# 04_Schematic.net
KiCad netlist of a schematic drawn in Altium Designer
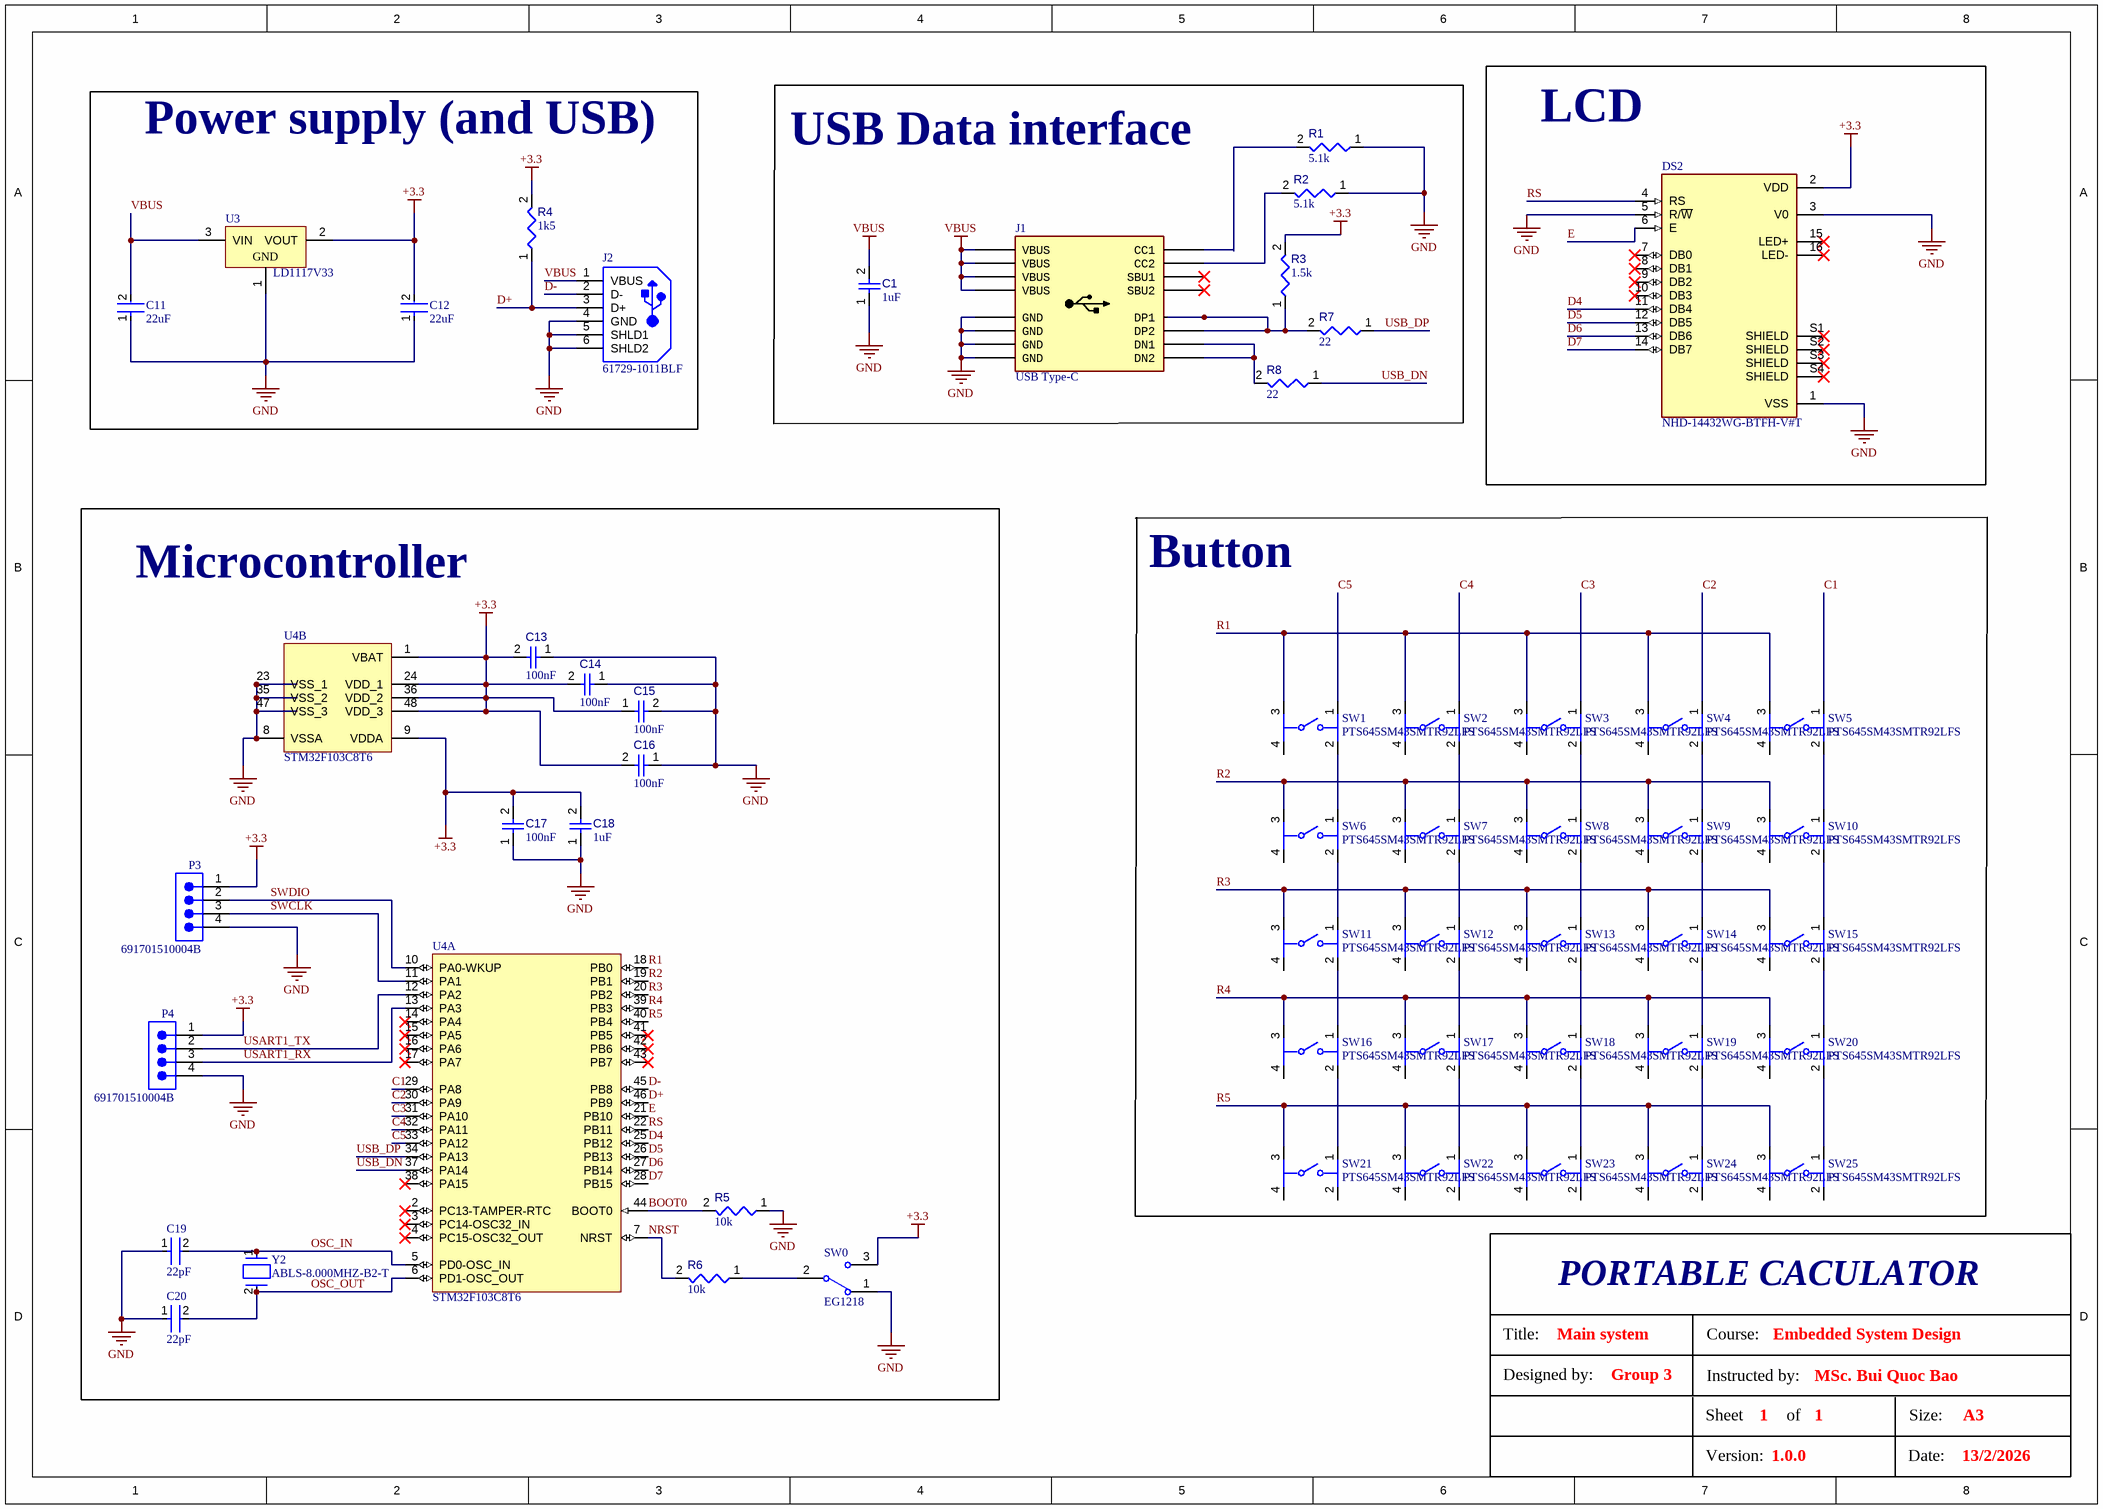
[diagram p0: 04_Schematic.SchDoc]

(export (version "E")
  (design (tool "Eeschema 10.0.6"))
  (components
    (comp (ref "C1")
      (value "1uF")
      (footprint "CAPC1005X56X25LL10T15")
      (description "Chip Capacitor, 0.1 uF, +/- 5%, 16 V, 0402 (1005 Metric)")
      (fields (field (name "TOLERANCE") "5%") (field (name "Comment") "Capacitor 0.1 uF +/- 5% 16 V 0402"))
      (libsource (lib "Nguyen Thaizeroxz") (part "CAP-NP-2"))
    )
    (comp (ref "C11")
      (value "22uF")
      (footprint "FP-RCE0K1-MFG")
      (description "Cap Ceramic 22pF 50V C0G ±5% Radial 5mm +125°C Automotive Bulk")
      (fields (field (name "TOLERANCE") "5%"))
      (libsource (lib "Altium Content Vault") (part "b4654b650e69147ec39a6b967a45e02"))
    )
    (comp (ref "C12")
      (value "22uF")
      (footprint "FP-RCE0K1-MFG")
      (description "Cap Ceramic 22pF 50V C0G ±5% Radial 5mm +125°C Automotive Bulk")
      (fields (field (name "TOLERANCE") "5%"))
      (libsource (lib "Altium Content Vault") (part "b4654b650e69147ec39a6b967a45e02"))
    )
    (comp (ref "C13")
      (value "100nF")
      (footprint "CAPC1005X56X25LL10T15")
      (description "Chip Capacitor, 0.1 uF, +/- 5%, 16 V, 0402 (1005 Metric)")
      (fields (field (name "TOLERANCE") "5%") (field (name "Comment") "Capacitor 0.1 uF +/- 5% 16 V 0402"))
      (libsource (lib "Nguyen Thaizeroxz") (part "CAP-NP-2"))
    )
    (comp (ref "C14")
      (value "100nF")
      (footprint "CAPC1005X56X25LL10T15")
      (description "Chip Capacitor, 0.1 uF, +/- 5%, 16 V, 0402 (1005 Metric)")
      (fields (field (name "TOLERANCE") "5%") (field (name "Comment") "Capacitor 0.1 uF +/- 5% 16 V 0402"))
      (libsource (lib "Nguyen Thaizeroxz") (part "CAP-NP-2"))
    )
    (comp (ref "C15")
      (value "100nF")
      (footprint "CAPC1005X56X25LL10T15")
      (description "Chip Capacitor, 0.1 uF, +/- 5%, 16 V, 0402 (1005 Metric)")
      (fields (field (name "TOLERANCE") "5%") (field (name "Comment") "Capacitor 0.1 uF +/- 5% 16 V 0402"))
      (libsource (lib "Nguyen Thaizeroxz") (part "CAP-NP-2"))
    )
    (comp (ref "C16")
      (value "100nF")
      (footprint "CAPC1005X56X25LL10T15")
      (description "Chip Capacitor, 0.1 uF, +/- 5%, 16 V, 0402 (1005 Metric)")
      (fields (field (name "TOLERANCE") "5%") (field (name "Comment") "Capacitor 0.1 uF +/- 5% 16 V 0402"))
      (libsource (lib "Nguyen Thaizeroxz") (part "CAP-NP-2"))
    )
    (comp (ref "C17")
      (value "100nF")
      (footprint "CAPC1005X56X25LL10T15")
      (description "Chip Capacitor, 0.1 uF, +/- 5%, 16 V, 0402 (1005 Metric)")
      (fields (field (name "TOLERANCE") "5%") (field (name "Comment") "Capacitor 0.1 uF +/- 5% 16 V 0402"))
      (libsource (lib "Nguyen Thaizeroxz") (part "CAP-NP-2"))
    )
    (comp (ref "C18")
      (value "1uF")
      (footprint "CAPC1005X56X25LL10T15")
      (description "Chip Capacitor, 0.1 uF, +/- 5%, 16 V, 0402 (1005 Metric)")
      (fields (field (name "TOLERANCE") "5%") (field (name "Comment") "Capacitor 0.1 uF +/- 5% 16 V 0402"))
      (libsource (lib "Nguyen Thaizeroxz") (part "CAP-NP-2"))
    )
    (comp (ref "C19")
      (value "22pF")
      (footprint "FP-RCE0K1-MFG")
      (description "Cap Ceramic 22pF 50V C0G ±5% Radial 5mm +125°C Automotive Bulk")
      (fields (field (name "TOLERANCE") "5%"))
      (libsource (lib "Altium Content Vault") (part "b4654b650e69147ec39a6b967a45e02"))
    )
    (comp (ref "C20")
      (value "22pF")
      (footprint "FP-RCE0K1-MFG")
      (description "Cap Ceramic 22pF 50V C0G ±5% Radial 5mm +125°C Automotive Bulk")
      (fields (field (name "TOLERANCE") "5%"))
      (libsource (lib "Altium Content Vault") (part "b4654b650e69147ec39a6b967a45e02"))
    )
    (comp (ref "DS2")
      (value "NHD-14432WG-BTFH-V#T")
      (footprint "LCD_NHD-14432WG-BTFH-V#T")
      (fields (field (name "MF") "Newhaven Display"))
      (libsource (lib "Nguyen Thaizeroxz") (part "NHD-14432WG-BTFH-V#T"))
    )
    (comp (ref "J1")
      (value "USB Type-C")
      (footprint "TYPE-C-16POS")
      (libsource (lib "Schlib1") (part "USB Type-C"))
    )
    (comp (ref "J2")
      (value "61729-1011BLF")
      (footprint "FCI-61729-1011BLF_V")
      (description "USB Receptacle B Type, Right Angle, 4 Position, Height 11.5 mm,-40 to 85 degC, RoHS, Tube")
      (fields (field (name "MANUFACTURER") "FCI Electronics"))
      (libsource (lib "Nguyen Thaizeroxz") (part "USB-4-2SHLD"))
    )
    (comp (ref "P3")
      (value "691701510004B")
      (footprint "691701510004B")
      (description "Terminal Block, 5.08MM, Close Vertical Pcb Header, Thr Type, 4 Pins")
      (libsource (lib "Altium Content Vault") (part "TBL - 1R - 04P - Male"))
    )
    (comp (ref "P4")
      (value "691701510004B")
      (footprint "691701510004B")
      (description "Terminal Block, 5.08MM, Close Vertical Pcb Header, Thr Type, 4 Pins")
      (libsource (lib "Altium Content Vault") (part "TBL - 1R - 04P - Male"))
    )
    (comp (ref "R1")
      (value "5.1k")
      (footprint "RESC0402(1005)_L")
      (description "Chip Resistor, 1 kOhms, +/-5 %, 63 mW, -55 to 155 degC, 0402")
      (fields (field (name "TOLERANCE") "5%") (field (name "POWER") "63mW"))
      (libsource (lib "Nguyen Thaizeroxz") (part "RES-2"))
    )
    (comp (ref "R2")
      (value "5.1k")
      (footprint "RESC0402(1005)_L")
      (description "Chip Resistor, 1 kOhms, +/-5 %, 63 mW, -55 to 155 degC, 0402")
      (fields (field (name "TOLERANCE") "5%") (field (name "POWER") "63mW"))
      (libsource (lib "Nguyen Thaizeroxz") (part "RES-2"))
    )
    (comp (ref "R3")
      (value "1.5k")
      (footprint "RESC0402(1005)_L")
      (description "Chip Resistor, 1 kOhms, +/-5 %, 63 mW, -55 to 155 degC, 0402")
      (fields (field (name "TOLERANCE") "5%") (field (name "POWER") "63mW"))
      (libsource (lib "Nguyen Thaizeroxz") (part "RES-2"))
    )
    (comp (ref "R4")
      (value "1k5")
      (footprint "RESC0402(1005)_L")
      (description "Chip Resistor, 1 kOhms, +/-5 %, 63 mW, -55 to 155 degC, 0402")
      (fields (field (name "TOLERANCE") "5%") (field (name "POWER") "63mW"))
      (libsource (lib "Nguyen Thaizeroxz") (part "RES-2"))
    )
    (comp (ref "R5")
      (value "10k")
      (footprint "RESC0402(1005)_L")
      (description "Chip Resistor, 1 kOhms, +/-5 %, 63 mW, -55 to 155 degC, 0402")
      (fields (field (name "TOLERANCE") "5%") (field (name "POWER") "63mW"))
      (libsource (lib "Nguyen Thaizeroxz") (part "RES-2"))
    )
    (comp (ref "R6")
      (value "10k")
      (footprint "RESC0402(1005)_L")
      (description "Chip Resistor, 1 kOhms, +/-5 %, 63 mW, -55 to 155 degC, 0402")
      (fields (field (name "TOLERANCE") "5%") (field (name "POWER") "63mW"))
      (libsource (lib "Nguyen Thaizeroxz") (part "RES-2"))
    )
    (comp (ref "R7")
      (value "22")
      (footprint "RESC0402(1005)_L")
      (description "Chip Resistor, 1 kOhms, +/-5 %, 63 mW, -55 to 155 degC, 0402")
      (fields (field (name "TOLERANCE") "5%") (field (name "POWER") "63mW"))
      (libsource (lib "Nguyen Thaizeroxz") (part "RES-2"))
    )
    (comp (ref "R8")
      (value "22")
      (footprint "RESC0402(1005)_L")
      (description "Chip Resistor, 1 kOhms, +/-5 %, 63 mW, -55 to 155 degC, 0402")
      (fields (field (name "TOLERANCE") "5%") (field (name "POWER") "63mW"))
      (libsource (lib "Nguyen Thaizeroxz") (part "RES-2"))
    )
    (comp (ref "SW0")
      (value "EG1218")
      (footprint "ESWI-EG1218_V")
      (description "Slide Switch, SPDT, 500 V, -20 to 70 degC, 3-Pin THD, RoHS, Bulk")
      (fields (field (name "MANUFACTURER") "E-Switch"))
      (libsource (lib "Nguyen Thaizeroxz") (part "SW-SPDT-3_B"))
    )
    (comp (ref "SW1")
      (value "PTS645SM43SMTR92LFS")
      (footprint "FP-PTS645SM43SMTR92LFS-MFG")
      (description "SWITCH TACTILE SPST-NO 0.05A 12V")
      (libsource (lib "Altium Content Vault") (part "1adf0dd01260c80cf25a44bfd6b99ba"))
    )
    (comp (ref "SW2")
      (value "PTS645SM43SMTR92LFS")
      (footprint "FP-PTS645SM43SMTR92LFS-MFG")
      (description "SWITCH TACTILE SPST-NO 0.05A 12V")
      (libsource (lib "Altium Content Vault") (part "1adf0dd01260c80cf25a44bfd6b99ba"))
    )
    (comp (ref "SW3")
      (value "PTS645SM43SMTR92LFS")
      (footprint "FP-PTS645SM43SMTR92LFS-MFG")
      (description "SWITCH TACTILE SPST-NO 0.05A 12V")
      (libsource (lib "Altium Content Vault") (part "1adf0dd01260c80cf25a44bfd6b99ba"))
    )
    (comp (ref "SW4")
      (value "PTS645SM43SMTR92LFS")
      (footprint "FP-PTS645SM43SMTR92LFS-MFG")
      (description "SWITCH TACTILE SPST-NO 0.05A 12V")
      (libsource (lib "Altium Content Vault") (part "1adf0dd01260c80cf25a44bfd6b99ba"))
    )
    (comp (ref "SW5")
      (value "PTS645SM43SMTR92LFS")
      (footprint "FP-PTS645SM43SMTR92LFS-MFG")
      (description "SWITCH TACTILE SPST-NO 0.05A 12V")
      (libsource (lib "Altium Content Vault") (part "1adf0dd01260c80cf25a44bfd6b99ba"))
    )
    (comp (ref "SW6")
      (value "PTS645SM43SMTR92LFS")
      (footprint "FP-PTS645SM43SMTR92LFS-MFG")
      (description "SWITCH TACTILE SPST-NO 0.05A 12V")
      (libsource (lib "Altium Content Vault") (part "1adf0dd01260c80cf25a44bfd6b99ba"))
    )
    (comp (ref "SW7")
      (value "PTS645SM43SMTR92LFS")
      (footprint "FP-PTS645SM43SMTR92LFS-MFG")
      (description "SWITCH TACTILE SPST-NO 0.05A 12V")
      (libsource (lib "Altium Content Vault") (part "1adf0dd01260c80cf25a44bfd6b99ba"))
    )
    (comp (ref "SW8")
      (value "PTS645SM43SMTR92LFS")
      (footprint "FP-PTS645SM43SMTR92LFS-MFG")
      (description "SWITCH TACTILE SPST-NO 0.05A 12V")
      (libsource (lib "Altium Content Vault") (part "1adf0dd01260c80cf25a44bfd6b99ba"))
    )
    (comp (ref "SW9")
      (value "PTS645SM43SMTR92LFS")
      (footprint "FP-PTS645SM43SMTR92LFS-MFG")
      (description "SWITCH TACTILE SPST-NO 0.05A 12V")
      (libsource (lib "Altium Content Vault") (part "1adf0dd01260c80cf25a44bfd6b99ba"))
    )
    (comp (ref "SW10")
      (value "PTS645SM43SMTR92LFS")
      (footprint "FP-PTS645SM43SMTR92LFS-MFG")
      (description "SWITCH TACTILE SPST-NO 0.05A 12V")
      (libsource (lib "Altium Content Vault") (part "1adf0dd01260c80cf25a44bfd6b99ba"))
    )
    (comp (ref "SW11")
      (value "PTS645SM43SMTR92LFS")
      (footprint "FP-PTS645SM43SMTR92LFS-MFG")
      (description "SWITCH TACTILE SPST-NO 0.05A 12V")
      (libsource (lib "Altium Content Vault") (part "1adf0dd01260c80cf25a44bfd6b99ba"))
    )
    (comp (ref "SW12")
      (value "PTS645SM43SMTR92LFS")
      (footprint "FP-PTS645SM43SMTR92LFS-MFG")
      (description "SWITCH TACTILE SPST-NO 0.05A 12V")
      (libsource (lib "Altium Content Vault") (part "1adf0dd01260c80cf25a44bfd6b99ba"))
    )
    (comp (ref "SW13")
      (value "PTS645SM43SMTR92LFS")
      (footprint "FP-PTS645SM43SMTR92LFS-MFG")
      (description "SWITCH TACTILE SPST-NO 0.05A 12V")
      (libsource (lib "Altium Content Vault") (part "1adf0dd01260c80cf25a44bfd6b99ba"))
    )
    (comp (ref "SW14")
      (value "PTS645SM43SMTR92LFS")
      (footprint "FP-PTS645SM43SMTR92LFS-MFG")
      (description "SWITCH TACTILE SPST-NO 0.05A 12V")
      (libsource (lib "Altium Content Vault") (part "1adf0dd01260c80cf25a44bfd6b99ba"))
    )
    (comp (ref "SW15")
      (value "PTS645SM43SMTR92LFS")
      (footprint "FP-PTS645SM43SMTR92LFS-MFG")
      (description "SWITCH TACTILE SPST-NO 0.05A 12V")
      (libsource (lib "Altium Content Vault") (part "1adf0dd01260c80cf25a44bfd6b99ba"))
    )
    (comp (ref "SW16")
      (value "PTS645SM43SMTR92LFS")
      (footprint "FP-PTS645SM43SMTR92LFS-MFG")
      (description "SWITCH TACTILE SPST-NO 0.05A 12V")
      (libsource (lib "Altium Content Vault") (part "1adf0dd01260c80cf25a44bfd6b99ba"))
    )
    (comp (ref "SW17")
      (value "PTS645SM43SMTR92LFS")
      (footprint "FP-PTS645SM43SMTR92LFS-MFG")
      (description "SWITCH TACTILE SPST-NO 0.05A 12V")
      (libsource (lib "Altium Content Vault") (part "1adf0dd01260c80cf25a44bfd6b99ba"))
    )
    (comp (ref "SW18")
      (value "PTS645SM43SMTR92LFS")
      (footprint "FP-PTS645SM43SMTR92LFS-MFG")
      (description "SWITCH TACTILE SPST-NO 0.05A 12V")
      (libsource (lib "Altium Content Vault") (part "1adf0dd01260c80cf25a44bfd6b99ba"))
    )
    (comp (ref "SW19")
      (value "PTS645SM43SMTR92LFS")
      (footprint "FP-PTS645SM43SMTR92LFS-MFG")
      (description "SWITCH TACTILE SPST-NO 0.05A 12V")
      (libsource (lib "Altium Content Vault") (part "1adf0dd01260c80cf25a44bfd6b99ba"))
    )
    (comp (ref "SW20")
      (value "PTS645SM43SMTR92LFS")
      (footprint "FP-PTS645SM43SMTR92LFS-MFG")
      (description "SWITCH TACTILE SPST-NO 0.05A 12V")
      (libsource (lib "Altium Content Vault") (part "1adf0dd01260c80cf25a44bfd6b99ba"))
    )
    (comp (ref "SW21")
      (value "PTS645SM43SMTR92LFS")
      (footprint "FP-PTS645SM43SMTR92LFS-MFG")
      (description "SWITCH TACTILE SPST-NO 0.05A 12V")
      (libsource (lib "Altium Content Vault") (part "1adf0dd01260c80cf25a44bfd6b99ba"))
    )
    (comp (ref "SW22")
      (value "PTS645SM43SMTR92LFS")
      (footprint "FP-PTS645SM43SMTR92LFS-MFG")
      (description "SWITCH TACTILE SPST-NO 0.05A 12V")
      (libsource (lib "Altium Content Vault") (part "1adf0dd01260c80cf25a44bfd6b99ba"))
    )
    (comp (ref "SW23")
      (value "PTS645SM43SMTR92LFS")
      (footprint "FP-PTS645SM43SMTR92LFS-MFG")
      (description "SWITCH TACTILE SPST-NO 0.05A 12V")
      (libsource (lib "Altium Content Vault") (part "1adf0dd01260c80cf25a44bfd6b99ba"))
    )
    (comp (ref "SW24")
      (value "PTS645SM43SMTR92LFS")
      (footprint "FP-PTS645SM43SMTR92LFS-MFG")
      (description "SWITCH TACTILE SPST-NO 0.05A 12V")
      (libsource (lib "Altium Content Vault") (part "1adf0dd01260c80cf25a44bfd6b99ba"))
    )
    (comp (ref "SW25")
      (value "PTS645SM43SMTR92LFS")
      (footprint "FP-PTS645SM43SMTR92LFS-MFG")
      (description "SWITCH TACTILE SPST-NO 0.05A 12V")
      (libsource (lib "Altium Content Vault") (part "1adf0dd01260c80cf25a44bfd6b99ba"))
    )
    (comp (ref "U3")
      (value "LD1117V33")
      (footprint "STM-TO220-3")
      (fields (field (name "MANUFACTURER") "STMicroelectronics") (field (name "POWER") "12W"))
      (libsource (lib "Nguyen Thaizeroxz") (part "STM-LD1117-V33"))
    )
    (comp (ref "U4")
      (value "STM32F103C8T6")
      (footprint "STM-LQFP48_M")
      (description "MCU 32-bit STM32F1 ARM Cortex M3 RISC 64KB Flash 2.5V/3.3V 48-Pin LQFP Tray")
      (libsource (lib "Nguyen Thaizeroxz") (part "MC-ARM-STM32F103X8_B-SQ48"))
    )
    (comp (ref "Y2")
      (value "ABLS-8.000MHZ-B2-T")
      (footprint "FP-ABLS-MFG")
      (description "CRYSTAL 8.0000MHZ 18PF SMD")
      (fields (field (name "TOLERANCE") "20ppm"))
      (libsource (lib "Altium Content Vault") (part "c23a69dc6c9e2f18f2079038eb95dd1"))
    )
  )
  (nets
    (net (code "1") (name "+3.3") (class "Default")
      (node (ref "C12") (pin "2") (pinfunction "2_2") (pintype "passive"))
      (node (ref "C13") (pin "2") (pinfunction "2_2") (pintype "passive"))
      (node (ref "C14") (pin "2") (pinfunction "2_2") (pintype "passive"))
      (node (ref "C15") (pin "1") (pinfunction "1_1") (pintype "passive"))
      (node (ref "C16") (pin "2") (pinfunction "2_2") (pintype "passive"))
      (node (ref "C17") (pin "2") (pinfunction "2_2") (pintype "passive"))
      (node (ref "C18") (pin "2") (pinfunction "2_2") (pintype "passive"))
      (node (ref "DS2") (pin "2") (pinfunction "VDD_2") (pintype "power_in"))
      (node (ref "P3") (pin "1") (pinfunction "1_1") (pintype "passive"))
      (node (ref "P4") (pin "1") (pinfunction "1_1") (pintype "passive"))
      (node (ref "R3") (pin "2") (pinfunction "2_2") (pintype "passive"))
      (node (ref "R4") (pin "2") (pinfunction "2_2") (pintype "passive"))
      (node (ref "SW0") (pin "3") (pinfunction "3_3") (pintype "passive"))
      (node (ref "U3") (pin "2") (pinfunction "VOUT_2") (pintype "power_in"))
      (node (ref "U4") (pin "1") (pinfunction "VBAT_1") (pintype "power_in"))
      (node (ref "U4") (pin "24") (pinfunction "VDD_1_24") (pintype "power_in"))
      (node (ref "U4") (pin "36") (pinfunction "VDD_2_36") (pintype "power_in"))
      (node (ref "U4") (pin "48") (pinfunction "VDD_3_48") (pintype "power_in"))
      (node (ref "U4") (pin "9") (pinfunction "VDDA_9") (pintype "power_in"))
    )
    (net (code "2") (name "/BOOT0") (class "Default")
      (node (ref "R5") (pin "2") (pinfunction "2_2") (pintype "passive"))
      (node (ref "U4") (pin "44") (pinfunction "BOOT0_44") (pintype "input"))
    )
    (net (code "3") (name "/C1") (class "Default")
      (node (ref "SW5") (pin "1") (pinfunction "1_1") (pintype "passive"))
      (node (ref "U4") (pin "29") (pinfunction "PA8_29") (pintype "bidirectional"))
    )
    (net (code "4") (name "/C2") (class "Default")
      (node (ref "SW4") (pin "1") (pinfunction "1_1") (pintype "passive"))
      (node (ref "U4") (pin "30") (pinfunction "PA9_30") (pintype "bidirectional"))
    )
    (net (code "5") (name "/C3") (class "Default")
      (node (ref "SW3") (pin "1") (pinfunction "1_1") (pintype "passive"))
      (node (ref "U4") (pin "31") (pinfunction "PA10_31") (pintype "bidirectional"))
    )
    (net (code "6") (name "/C4") (class "Default")
      (node (ref "SW2") (pin "1") (pinfunction "1_1") (pintype "passive"))
      (node (ref "U4") (pin "32") (pinfunction "PA11_32") (pintype "bidirectional"))
    )
    (net (code "7") (name "/C5") (class "Default")
      (node (ref "SW1") (pin "1") (pinfunction "1_1") (pintype "passive"))
      (node (ref "U4") (pin "33") (pinfunction "PA12_33") (pintype "bidirectional"))
    )
    (net (code "8") (name "/D+") (class "Default")
      (node (ref "J2") (pin "3") (pinfunction "D+_3") (pintype "passive"))
      (node (ref "R4") (pin "1") (pinfunction "1_1") (pintype "passive"))
      (node (ref "U4") (pin "46") (pinfunction "PB9_46") (pintype "bidirectional"))
    )
    (net (code "9") (name "/D-") (class "Default")
      (node (ref "J2") (pin "2") (pinfunction "D-_2") (pintype "passive"))
      (node (ref "U4") (pin "45") (pinfunction "PB8_45") (pintype "bidirectional"))
    )
    (net (code "10") (name "/D4") (class "Default")
      (node (ref "DS2") (pin "11") (pinfunction "DB4_11") (pintype "bidirectional"))
      (node (ref "U4") (pin "25") (pinfunction "PB12_25") (pintype "bidirectional"))
    )
    (net (code "11") (name "/D5") (class "Default")
      (node (ref "DS2") (pin "12") (pinfunction "DB5_12") (pintype "bidirectional"))
      (node (ref "U4") (pin "26") (pinfunction "PB13_26") (pintype "bidirectional"))
    )
    (net (code "12") (name "/D6") (class "Default")
      (node (ref "DS2") (pin "13") (pinfunction "DB6_13") (pintype "bidirectional"))
      (node (ref "U4") (pin "27") (pinfunction "PB14_27") (pintype "bidirectional"))
    )
    (net (code "13") (name "/D7") (class "Default")
      (node (ref "DS2") (pin "14") (pinfunction "DB7_14") (pintype "bidirectional"))
      (node (ref "U4") (pin "28") (pinfunction "PB15_28") (pintype "bidirectional"))
    )
    (net (code "14") (name "/E") (class "Default")
      (node (ref "DS2") (pin "6") (pinfunction "E_6") (pintype "input"))
      (node (ref "U4") (pin "21") (pinfunction "PB10_21") (pintype "bidirectional"))
    )
    (net (code "15") (name "/NRST") (class "Default")
      (node (ref "R6") (pin "2") (pinfunction "2_2") (pintype "passive"))
      (node (ref "U4") (pin "7") (pinfunction "NRST_7") (pintype "bidirectional"))
    )
    (net (code "16") (name "/OSC_IN") (class "Default")
      (node (ref "C19") (pin "2") (pinfunction "2_2") (pintype "passive"))
      (node (ref "U4") (pin "5") (pinfunction "PD0-OSC_IN_5") (pintype "bidirectional"))
      (node (ref "Y2") (pin "1") (pinfunction "1_1") (pintype "passive"))
    )
    (net (code "17") (name "/OSC_OUT") (class "Default")
      (node (ref "C20") (pin "2") (pinfunction "2_2") (pintype "passive"))
      (node (ref "U4") (pin "6") (pinfunction "PD1-OSC_OUT_6") (pintype "bidirectional"))
      (node (ref "Y2") (pin "2") (pinfunction "2_2") (pintype "passive"))
    )
    (net (code "18") (name "/R1") (class "Default")
      (node (ref "SW1") (pin "3") (pinfunction "3_3") (pintype "passive"))
      (node (ref "SW2") (pin "3") (pinfunction "3_3") (pintype "passive"))
      (node (ref "SW3") (pin "3") (pinfunction "3_3") (pintype "passive"))
      (node (ref "SW4") (pin "3") (pinfunction "3_3") (pintype "passive"))
      (node (ref "SW5") (pin "3") (pinfunction "3_3") (pintype "passive"))
      (node (ref "U4") (pin "18") (pinfunction "PB0_18") (pintype "bidirectional"))
    )
    (net (code "19") (name "/R2") (class "Default")
      (node (ref "SW10") (pin "3") (pinfunction "3_3") (pintype "passive"))
      (node (ref "SW6") (pin "3") (pinfunction "3_3") (pintype "passive"))
      (node (ref "SW7") (pin "3") (pinfunction "3_3") (pintype "passive"))
      (node (ref "SW8") (pin "3") (pinfunction "3_3") (pintype "passive"))
      (node (ref "SW9") (pin "3") (pinfunction "3_3") (pintype "passive"))
      (node (ref "U4") (pin "19") (pinfunction "PB1_19") (pintype "bidirectional"))
    )
    (net (code "20") (name "/R3") (class "Default")
      (node (ref "SW11") (pin "3") (pinfunction "3_3") (pintype "passive"))
      (node (ref "SW12") (pin "3") (pinfunction "3_3") (pintype "passive"))
      (node (ref "SW13") (pin "3") (pinfunction "3_3") (pintype "passive"))
      (node (ref "SW14") (pin "3") (pinfunction "3_3") (pintype "passive"))
      (node (ref "SW15") (pin "3") (pinfunction "3_3") (pintype "passive"))
      (node (ref "U4") (pin "20") (pinfunction "PB2_20") (pintype "bidirectional"))
    )
    (net (code "21") (name "/R4") (class "Default")
      (node (ref "SW16") (pin "3") (pinfunction "3_3") (pintype "passive"))
      (node (ref "SW17") (pin "3") (pinfunction "3_3") (pintype "passive"))
      (node (ref "SW18") (pin "3") (pinfunction "3_3") (pintype "passive"))
      (node (ref "SW19") (pin "3") (pinfunction "3_3") (pintype "passive"))
      (node (ref "SW20") (pin "3") (pinfunction "3_3") (pintype "passive"))
      (node (ref "U4") (pin "39") (pinfunction "PB3_39") (pintype "bidirectional"))
    )
    (net (code "22") (name "/R5") (class "Default")
      (node (ref "SW21") (pin "3") (pinfunction "3_3") (pintype "passive"))
      (node (ref "SW22") (pin "3") (pinfunction "3_3") (pintype "passive"))
      (node (ref "SW23") (pin "3") (pinfunction "3_3") (pintype "passive"))
      (node (ref "SW24") (pin "3") (pinfunction "3_3") (pintype "passive"))
      (node (ref "SW25") (pin "3") (pinfunction "3_3") (pintype "passive"))
      (node (ref "U4") (pin "40") (pinfunction "PB4_40") (pintype "bidirectional"))
    )
    (net (code "23") (name "/RS") (class "Default")
      (node (ref "DS2") (pin "4") (pinfunction "RS_4") (pintype "input"))
      (node (ref "U4") (pin "22") (pinfunction "PB11_22") (pintype "bidirectional"))
    )
    (net (code "24") (name "/SWCLK") (class "Default")
      (node (ref "P3") (pin "3") (pinfunction "3_3") (pintype "passive"))
      (node (ref "U4") (pin "11") (pinfunction "PA1_11") (pintype "bidirectional"))
    )
    (net (code "25") (name "/SWDIO") (class "Default")
      (node (ref "P3") (pin "2") (pinfunction "2_2") (pintype "passive"))
      (node (ref "U4") (pin "10") (pinfunction "PA0-WKUP_10") (pintype "bidirectional"))
    )
    (net (code "26") (name "/USART1_RX") (class "Default")
      (node (ref "P4") (pin "3") (pinfunction "3_3") (pintype "passive"))
      (node (ref "U4") (pin "13") (pinfunction "PA3_13") (pintype "bidirectional"))
    )
    (net (code "27") (name "/USART1_TX") (class "Default")
      (node (ref "P4") (pin "2") (pinfunction "2_2") (pintype "passive"))
      (node (ref "U4") (pin "12") (pinfunction "PA2_12") (pintype "bidirectional"))
    )
    (net (code "28") (name "/USB_DN") (class "Default")
      (node (ref "R8") (pin "1") (pinfunction "1_1") (pintype "passive"))
      (node (ref "U4") (pin "37") (pinfunction "PA14_37") (pintype "bidirectional"))
    )
    (net (code "29") (name "/USB_DP") (class "Default")
      (node (ref "R7") (pin "1") (pinfunction "1_1") (pintype "passive"))
      (node (ref "U4") (pin "34") (pinfunction "PA13_34") (pintype "bidirectional"))
    )
    (net (code "30") (name "GND") (class "Default")
      (node (ref "C1") (pin "1") (pinfunction "1_1") (pintype "passive"))
      (node (ref "C11") (pin "1") (pinfunction "1_1") (pintype "passive"))
      (node (ref "C12") (pin "1") (pinfunction "1_1") (pintype "passive"))
      (node (ref "C13") (pin "1") (pinfunction "1_1") (pintype "passive"))
      (node (ref "C14") (pin "1") (pinfunction "1_1") (pintype "passive"))
      (node (ref "C15") (pin "2") (pinfunction "2_2") (pintype "passive"))
      (node (ref "C16") (pin "1") (pinfunction "1_1") (pintype "passive"))
      (node (ref "C17") (pin "1") (pinfunction "1_1") (pintype "passive"))
      (node (ref "C18") (pin "1") (pinfunction "1_1") (pintype "passive"))
      (node (ref "C19") (pin "1") (pinfunction "1_1") (pintype "passive"))
      (node (ref "C20") (pin "1") (pinfunction "1_1") (pintype "passive"))
      (node (ref "DS2") (pin "1") (pinfunction "VSS_1") (pintype "power_in"))
      (node (ref "DS2") (pin "3") (pinfunction "V0_3") (pintype "passive"))
      (node (ref "DS2") (pin "5") (pinfunction "R/~{W}_5") (pintype "input"))
      (node (ref "J1") (pin "A12_B1") (pinfunction "GND_A12_B1") (pintype "passive"))
      (node (ref "J1") (pin "A1_B12") (pinfunction "GND_A1_B12") (pintype "passive"))
      (node (ref "J2") (pin "4") (pinfunction "GND_4") (pintype "passive"))
      (node (ref "J2") (pin "5") (pinfunction "SHLD1_5") (pintype "passive"))
      (node (ref "J2") (pin "6") (pinfunction "SHLD2_6") (pintype "passive"))
      (node (ref "P3") (pin "4") (pinfunction "4_4") (pintype "passive"))
      (node (ref "P4") (pin "4") (pinfunction "4_4") (pintype "passive"))
      (node (ref "R1") (pin "1") (pinfunction "1_1") (pintype "passive"))
      (node (ref "R2") (pin "1") (pinfunction "1_1") (pintype "passive"))
      (node (ref "R5") (pin "1") (pinfunction "1_1") (pintype "passive"))
      (node (ref "SW0") (pin "1") (pinfunction "1_1") (pintype "passive"))
      (node (ref "U3") (pin "1") (pinfunction "GND_1") (pintype "power_in"))
      (node (ref "U4") (pin "23") (pinfunction "VSS_1_23") (pintype "power_in"))
      (node (ref "U4") (pin "35") (pinfunction "VSS_2_35") (pintype "power_in"))
      (node (ref "U4") (pin "47") (pinfunction "VSS_3_47") (pintype "power_in"))
      (node (ref "U4") (pin "8") (pinfunction "VSSA_8") (pintype "power_in"))
    )
    (net (code "31") (name "Net-(J1-CC2)") (class "Default")
      (node (ref "J1") (pin "B5") (pinfunction "CC2_B5") (pintype "passive"))
      (node (ref "R2") (pin "2") (pinfunction "2_2") (pintype "passive"))
    )
    (net (code "32") (name "Net-(J1-DN1)") (class "Default")
      (node (ref "J1") (pin "A7") (pinfunction "DN1_A7") (pintype "passive"))
      (node (ref "J1") (pin "B7") (pinfunction "DN2_B7") (pintype "passive"))
      (node (ref "R8") (pin "2") (pinfunction "2_2") (pintype "passive"))
    )
    (net (code "33") (name "Net-(J1-DP1)") (class "Default")
      (node (ref "J1") (pin "A6") (pinfunction "DP1_A6") (pintype "passive"))
      (node (ref "J1") (pin "B6") (pinfunction "DP2_B6") (pintype "passive"))
      (node (ref "R3") (pin "1") (pinfunction "1_1") (pintype "passive"))
      (node (ref "R7") (pin "2") (pinfunction "2_2") (pintype "passive"))
    )
    (net (code "34") (name "Net-(SW0-COM)") (class "Default")
      (node (ref "R6") (pin "1") (pinfunction "1_1") (pintype "passive"))
      (node (ref "SW0") (pin "2") (pinfunction "COM_2") (pintype "passive"))
    )
    (net (code "35") (name "Net-(SW1-Pad2)") (class "Default")
      (node (ref "SW1") (pin "2") (pinfunction "2_2") (pintype "passive"))
      (node (ref "SW6") (pin "1") (pinfunction "1_1") (pintype "passive"))
    )
    (net (code "36") (name "Net-(SW2-Pad2)") (class "Default")
      (node (ref "SW2") (pin "2") (pinfunction "2_2") (pintype "passive"))
      (node (ref "SW7") (pin "1") (pinfunction "1_1") (pintype "passive"))
    )
    (net (code "37") (name "Net-(SW3-Pad2)") (class "Default")
      (node (ref "SW3") (pin "2") (pinfunction "2_2") (pintype "passive"))
      (node (ref "SW8") (pin "1") (pinfunction "1_1") (pintype "passive"))
    )
    (net (code "38") (name "Net-(SW4-Pad2)") (class "Default")
      (node (ref "SW4") (pin "2") (pinfunction "2_2") (pintype "passive"))
      (node (ref "SW9") (pin "1") (pinfunction "1_1") (pintype "passive"))
    )
    (net (code "39") (name "Net-(SW10-Pad1)") (class "Default")
      (node (ref "SW10") (pin "1") (pinfunction "1_1") (pintype "passive"))
      (node (ref "SW5") (pin "2") (pinfunction "2_2") (pintype "passive"))
    )
    (net (code "40") (name "Net-(SW10-Pad2)") (class "Default")
      (node (ref "SW10") (pin "2") (pinfunction "2_2") (pintype "passive"))
      (node (ref "SW15") (pin "1") (pinfunction "1_1") (pintype "passive"))
    )
    (net (code "41") (name "Net-(SW11-Pad1)") (class "Default")
      (node (ref "SW11") (pin "1") (pinfunction "1_1") (pintype "passive"))
      (node (ref "SW6") (pin "2") (pinfunction "2_2") (pintype "passive"))
    )
    (net (code "42") (name "Net-(SW11-Pad2)") (class "Default")
      (node (ref "SW11") (pin "2") (pinfunction "2_2") (pintype "passive"))
      (node (ref "SW16") (pin "1") (pinfunction "1_1") (pintype "passive"))
    )
    (net (code "43") (name "Net-(SW12-Pad1)") (class "Default")
      (node (ref "SW12") (pin "1") (pinfunction "1_1") (pintype "passive"))
      (node (ref "SW7") (pin "2") (pinfunction "2_2") (pintype "passive"))
    )
    (net (code "44") (name "Net-(SW12-Pad2)") (class "Default")
      (node (ref "SW12") (pin "2") (pinfunction "2_2") (pintype "passive"))
      (node (ref "SW17") (pin "1") (pinfunction "1_1") (pintype "passive"))
    )
    (net (code "45") (name "Net-(SW13-Pad1)") (class "Default")
      (node (ref "SW13") (pin "1") (pinfunction "1_1") (pintype "passive"))
      (node (ref "SW8") (pin "2") (pinfunction "2_2") (pintype "passive"))
    )
    (net (code "46") (name "Net-(SW13-Pad2)") (class "Default")
      (node (ref "SW13") (pin "2") (pinfunction "2_2") (pintype "passive"))
      (node (ref "SW18") (pin "1") (pinfunction "1_1") (pintype "passive"))
    )
    (net (code "47") (name "Net-(SW14-Pad1)") (class "Default")
      (node (ref "SW14") (pin "1") (pinfunction "1_1") (pintype "passive"))
      (node (ref "SW9") (pin "2") (pinfunction "2_2") (pintype "passive"))
    )
    (net (code "48") (name "Net-(SW14-Pad2)") (class "Default")
      (node (ref "SW14") (pin "2") (pinfunction "2_2") (pintype "passive"))
      (node (ref "SW19") (pin "1") (pinfunction "1_1") (pintype "passive"))
    )
    (net (code "49") (name "Net-(SW15-Pad2)") (class "Default")
      (node (ref "SW15") (pin "2") (pinfunction "2_2") (pintype "passive"))
      (node (ref "SW20") (pin "1") (pinfunction "1_1") (pintype "passive"))
    )
    (net (code "50") (name "Net-(SW16-Pad2)") (class "Default")
      (node (ref "SW16") (pin "2") (pinfunction "2_2") (pintype "passive"))
      (node (ref "SW21") (pin "1") (pinfunction "1_1") (pintype "passive"))
    )
    (net (code "51") (name "Net-(SW17-Pad2)") (class "Default")
      (node (ref "SW17") (pin "2") (pinfunction "2_2") (pintype "passive"))
      (node (ref "SW22") (pin "1") (pinfunction "1_1") (pintype "passive"))
    )
    (net (code "52") (name "Net-(SW18-Pad2)") (class "Default")
      (node (ref "SW18") (pin "2") (pinfunction "2_2") (pintype "passive"))
      (node (ref "SW23") (pin "1") (pinfunction "1_1") (pintype "passive"))
    )
    (net (code "53") (name "Net-(SW19-Pad2)") (class "Default")
      (node (ref "SW19") (pin "2") (pinfunction "2_2") (pintype "passive"))
      (node (ref "SW24") (pin "1") (pinfunction "1_1") (pintype "passive"))
    )
    (net (code "54") (name "Net-(SW20-Pad2)") (class "Default")
      (node (ref "SW20") (pin "2") (pinfunction "2_2") (pintype "passive"))
      (node (ref "SW25") (pin "1") (pinfunction "1_1") (pintype "passive"))
    )
    (net (code "55") (name "VBUS") (class "Default")
      (node (ref "C1") (pin "2") (pinfunction "2_2") (pintype "passive"))
      (node (ref "C11") (pin "2") (pinfunction "2_2") (pintype "passive"))
      (node (ref "J1") (pin "A4_B9") (pinfunction "VBUS_A4_B9") (pintype "passive"))
      (node (ref "J1") (pin "A9_B4") (pinfunction "VBUS_A9_B4") (pintype "passive"))
      (node (ref "J2") (pin "1") (pinfunction "VBUS_1") (pintype "passive"))
      (node (ref "U3") (pin "3") (pinfunction "VIN_3") (pintype "power_in"))
    )
    (net (code "56") (name "unconnected-(DS2-DB0-Pad7)") (class "Default")
      (node (ref "DS2") (pin "7") (pinfunction "DB0_7") (pintype "bidirectional+no_connect"))
    )
    (net (code "57") (name "unconnected-(DS2-DB1-Pad8)") (class "Default")
      (node (ref "DS2") (pin "8") (pinfunction "DB1_8") (pintype "bidirectional+no_connect"))
    )
    (net (code "58") (name "unconnected-(DS2-DB2-Pad9)") (class "Default")
      (node (ref "DS2") (pin "9") (pinfunction "DB2_9") (pintype "bidirectional+no_connect"))
    )
    (net (code "59") (name "unconnected-(DS2-DB3-Pad10)") (class "Default")
      (node (ref "DS2") (pin "10") (pinfunction "DB3_10") (pintype "bidirectional+no_connect"))
    )
    (net (code "60") (name "unconnected-(DS2-LED+-Pad15)") (class "Default")
      (node (ref "DS2") (pin "15") (pinfunction "LED+_15") (pintype "passive+no_connect"))
    )
    (net (code "61") (name "unconnected-(DS2-LED--Pad16)") (class "Default")
      (node (ref "DS2") (pin "16") (pinfunction "LED-_16") (pintype "passive+no_connect"))
    )
    (net (code "62") (name "unconnected-(DS2-SHIELD-PadS1)") (class "Default")
      (node (ref "DS2") (pin "S1") (pinfunction "SHIELD_S1") (pintype "passive+no_connect"))
    )
    (net (code "63") (name "unconnected-(DS2-SHIELD-PadS2)") (class "Default")
      (node (ref "DS2") (pin "S2") (pinfunction "SHIELD_S2") (pintype "passive+no_connect"))
    )
    (net (code "64") (name "unconnected-(DS2-SHIELD-PadS3)") (class "Default")
      (node (ref "DS2") (pin "S3") (pinfunction "SHIELD_S3") (pintype "passive+no_connect"))
    )
    (net (code "65") (name "unconnected-(DS2-SHIELD-PadS4)") (class "Default")
      (node (ref "DS2") (pin "S4") (pinfunction "SHIELD_S4") (pintype "passive+no_connect"))
    )
    (net (code "66") (name "unconnected-(J1-CC1-PadA5)") (class "Default")
      (node (ref "J1") (pin "A5") (pinfunction "CC1_A5") (pintype "passive"))
    )
    (net (code "67") (name "unconnected-(J1-SBU1-PadA8)") (class "Default")
      (node (ref "J1") (pin "A8") (pinfunction "SBU1_A8") (pintype "passive+no_connect"))
    )
    (net (code "68") (name "unconnected-(J1-SBU2-PadB8)") (class "Default")
      (node (ref "J1") (pin "B8") (pinfunction "SBU2_B8") (pintype "passive+no_connect"))
    )
    (net (code "69") (name "unconnected-(R1-Pad2)") (class "Default")
      (node (ref "R1") (pin "2") (pinfunction "2_2") (pintype "passive"))
    )
    (net (code "70") (name "unconnected-(SW1-Pad4)") (class "Default")
      (node (ref "SW1") (pin "4") (pinfunction "4_4") (pintype "passive"))
    )
    (net (code "71") (name "unconnected-(SW2-Pad4)") (class "Default")
      (node (ref "SW2") (pin "4") (pinfunction "4_4") (pintype "passive"))
    )
    (net (code "72") (name "unconnected-(SW3-Pad4)") (class "Default")
      (node (ref "SW3") (pin "4") (pinfunction "4_4") (pintype "passive"))
    )
    (net (code "73") (name "unconnected-(SW4-Pad4)") (class "Default")
      (node (ref "SW4") (pin "4") (pinfunction "4_4") (pintype "passive"))
    )
    (net (code "74") (name "unconnected-(SW5-Pad4)") (class "Default")
      (node (ref "SW5") (pin "4") (pinfunction "4_4") (pintype "passive"))
    )
    (net (code "75") (name "unconnected-(SW6-Pad4)") (class "Default")
      (node (ref "SW6") (pin "4") (pinfunction "4_4") (pintype "passive"))
    )
    (net (code "76") (name "unconnected-(SW7-Pad4)") (class "Default")
      (node (ref "SW7") (pin "4") (pinfunction "4_4") (pintype "passive"))
    )
    (net (code "77") (name "unconnected-(SW8-Pad4)") (class "Default")
      (node (ref "SW8") (pin "4") (pinfunction "4_4") (pintype "passive"))
    )
    (net (code "78") (name "unconnected-(SW9-Pad4)") (class "Default")
      (node (ref "SW9") (pin "4") (pinfunction "4_4") (pintype "passive"))
    )
    (net (code "79") (name "unconnected-(SW10-Pad4)") (class "Default")
      (node (ref "SW10") (pin "4") (pinfunction "4_4") (pintype "passive"))
    )
    (net (code "80") (name "unconnected-(SW11-Pad4)") (class "Default")
      (node (ref "SW11") (pin "4") (pinfunction "4_4") (pintype "passive"))
    )
    (net (code "81") (name "unconnected-(SW12-Pad4)") (class "Default")
      (node (ref "SW12") (pin "4") (pinfunction "4_4") (pintype "passive"))
    )
    (net (code "82") (name "unconnected-(SW13-Pad4)") (class "Default")
      (node (ref "SW13") (pin "4") (pinfunction "4_4") (pintype "passive"))
    )
    (net (code "83") (name "unconnected-(SW14-Pad4)") (class "Default")
      (node (ref "SW14") (pin "4") (pinfunction "4_4") (pintype "passive"))
    )
    (net (code "84") (name "unconnected-(SW15-Pad4)") (class "Default")
      (node (ref "SW15") (pin "4") (pinfunction "4_4") (pintype "passive"))
    )
    (net (code "85") (name "unconnected-(SW16-Pad4)") (class "Default")
      (node (ref "SW16") (pin "4") (pinfunction "4_4") (pintype "passive"))
    )
    (net (code "86") (name "unconnected-(SW17-Pad4)") (class "Default")
      (node (ref "SW17") (pin "4") (pinfunction "4_4") (pintype "passive"))
    )
    (net (code "87") (name "unconnected-(SW18-Pad4)") (class "Default")
      (node (ref "SW18") (pin "4") (pinfunction "4_4") (pintype "passive"))
    )
    (net (code "88") (name "unconnected-(SW19-Pad4)") (class "Default")
      (node (ref "SW19") (pin "4") (pinfunction "4_4") (pintype "passive"))
    )
    (net (code "89") (name "unconnected-(SW20-Pad4)") (class "Default")
      (node (ref "SW20") (pin "4") (pinfunction "4_4") (pintype "passive"))
    )
    (net (code "90") (name "unconnected-(SW21-Pad2)") (class "Default")
      (node (ref "SW21") (pin "2") (pinfunction "2_2") (pintype "passive"))
    )
    (net (code "91") (name "unconnected-(SW21-Pad4)") (class "Default")
      (node (ref "SW21") (pin "4") (pinfunction "4_4") (pintype "passive"))
    )
    (net (code "92") (name "unconnected-(SW22-Pad2)") (class "Default")
      (node (ref "SW22") (pin "2") (pinfunction "2_2") (pintype "passive"))
    )
    (net (code "93") (name "unconnected-(SW22-Pad4)") (class "Default")
      (node (ref "SW22") (pin "4") (pinfunction "4_4") (pintype "passive"))
    )
    (net (code "94") (name "unconnected-(SW23-Pad2)") (class "Default")
      (node (ref "SW23") (pin "2") (pinfunction "2_2") (pintype "passive"))
    )
    (net (code "95") (name "unconnected-(SW23-Pad4)") (class "Default")
      (node (ref "SW23") (pin "4") (pinfunction "4_4") (pintype "passive"))
    )
    (net (code "96") (name "unconnected-(SW24-Pad2)") (class "Default")
      (node (ref "SW24") (pin "2") (pinfunction "2_2") (pintype "passive"))
    )
    (net (code "97") (name "unconnected-(SW24-Pad4)") (class "Default")
      (node (ref "SW24") (pin "4") (pinfunction "4_4") (pintype "passive"))
    )
    (net (code "98") (name "unconnected-(SW25-Pad2)") (class "Default")
      (node (ref "SW25") (pin "2") (pinfunction "2_2") (pintype "passive"))
    )
    (net (code "99") (name "unconnected-(SW25-Pad4)") (class "Default")
      (node (ref "SW25") (pin "4") (pinfunction "4_4") (pintype "passive"))
    )
    (net (code "100") (name "unconnected-(U4A-PA4-Pad14)") (class "Default")
      (node (ref "U4") (pin "14") (pinfunction "PA4_14") (pintype "bidirectional+no_connect"))
    )
    (net (code "101") (name "unconnected-(U4A-PA5-Pad15)") (class "Default")
      (node (ref "U4") (pin "15") (pinfunction "PA5_15") (pintype "bidirectional+no_connect"))
    )
    (net (code "102") (name "unconnected-(U4A-PA6-Pad16)") (class "Default")
      (node (ref "U4") (pin "16") (pinfunction "PA6_16") (pintype "bidirectional+no_connect"))
    )
    (net (code "103") (name "unconnected-(U4A-PA7-Pad17)") (class "Default")
      (node (ref "U4") (pin "17") (pinfunction "PA7_17") (pintype "bidirectional+no_connect"))
    )
    (net (code "104") (name "unconnected-(U4A-PA15-Pad38)") (class "Default")
      (node (ref "U4") (pin "38") (pinfunction "PA15_38") (pintype "bidirectional+no_connect"))
    )
    (net (code "105") (name "unconnected-(U4A-PB5-Pad41)") (class "Default")
      (node (ref "U4") (pin "41") (pinfunction "PB5_41") (pintype "bidirectional+no_connect"))
    )
    (net (code "106") (name "unconnected-(U4A-PB6-Pad42)") (class "Default")
      (node (ref "U4") (pin "42") (pinfunction "PB6_42") (pintype "bidirectional+no_connect"))
    )
    (net (code "107") (name "unconnected-(U4A-PB7-Pad43)") (class "Default")
      (node (ref "U4") (pin "43") (pinfunction "PB7_43") (pintype "bidirectional+no_connect"))
    )
    (net (code "108") (name "unconnected-(U4A-PC13-TAMPER-RTC-Pad2)") (class "Default")
      (node (ref "U4") (pin "2") (pinfunction "PC13-TAMPER-RTC_2") (pintype "bidirectional+no_connect"))
    )
    (net (code "109") (name "unconnected-(U4A-PC14-OSC32_IN-Pad3)") (class "Default")
      (node (ref "U4") (pin "3") (pinfunction "PC14-OSC32_IN_3") (pintype "bidirectional+no_connect"))
    )
    (net (code "110") (name "unconnected-(U4A-PC15-OSC32_OUT-Pad4)") (class "Default")
      (node (ref "U4") (pin "4") (pinfunction "PC15-OSC32_OUT_4") (pintype "bidirectional+no_connect"))
    )
  )
)
